# slidi.net
KiCad netlist of a schematic drawn in EAGLE
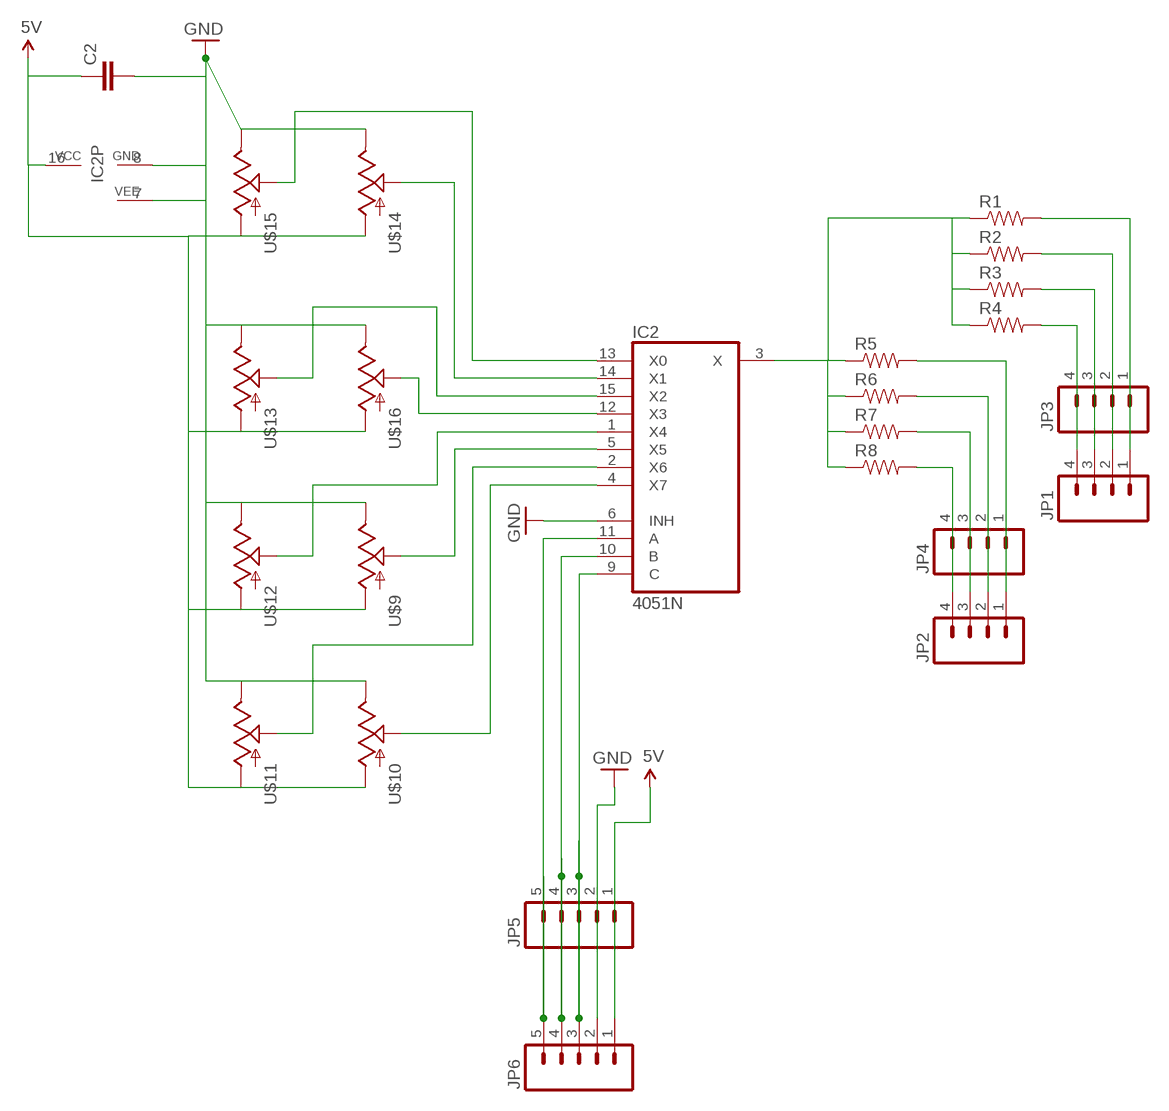
[diagram p0: schematic, sheet 1]

(export (version "E")
  (design (tool "Eeschema 10.0.6"))
  (components
    (comp (ref "C2")
      (value "CAPPTH")
      (footprint "eagle-import:CAP-PTH-SMALL")
      (libsource (lib "eagle-import") (part "CAPPTH"))
    )
    (comp (ref "IC2")
      (value "4051N")
      (footprint "eagle-import:DIL16")
      (libsource (lib "eagle-import") (part "4051N"))
    )
    (comp (ref "JP1")
      (value "M04PTH")
      (footprint "eagle-import:1X04")
      (libsource (lib "eagle-import") (part "M04PTH"))
    )
    (comp (ref "JP2")
      (value "M04PTH")
      (footprint "eagle-import:1X04")
      (libsource (lib "eagle-import") (part "M04PTH"))
    )
    (comp (ref "JP3")
      (value "M04PTH")
      (footprint "eagle-import:1X04")
      (libsource (lib "eagle-import") (part "M04PTH"))
    )
    (comp (ref "JP4")
      (value "M04PTH")
      (footprint "eagle-import:1X04")
      (libsource (lib "eagle-import") (part "M04PTH"))
    )
    (comp (ref "JP5")
      (value "M05PTH")
      (footprint "eagle-import:1X05")
      (libsource (lib "eagle-import") (part "M05PTH"))
    )
    (comp (ref "JP6")
      (value "M05PTH")
      (footprint "eagle-import:1X05")
      (libsource (lib "eagle-import") (part "M05PTH"))
    )
    (comp (ref "R1")
      (value "RESISTORAXIAL-0.3")
      (footprint "eagle-import:AXIAL-0.3")
      (libsource (lib "eagle-import") (part "RESISTORAXIAL-0.3"))
    )
    (comp (ref "R2")
      (value "RESISTORAXIAL-0.3")
      (footprint "eagle-import:AXIAL-0.3")
      (libsource (lib "eagle-import") (part "RESISTORAXIAL-0.3"))
    )
    (comp (ref "R3")
      (value "RESISTORAXIAL-0.3")
      (footprint "eagle-import:AXIAL-0.3")
      (libsource (lib "eagle-import") (part "RESISTORAXIAL-0.3"))
    )
    (comp (ref "R4")
      (value "RESISTORAXIAL-0.3")
      (footprint "eagle-import:AXIAL-0.3")
      (libsource (lib "eagle-import") (part "RESISTORAXIAL-0.3"))
    )
    (comp (ref "R5")
      (value "RESISTORAXIAL-0.3")
      (footprint "eagle-import:AXIAL-0.3")
      (libsource (lib "eagle-import") (part "RESISTORAXIAL-0.3"))
    )
    (comp (ref "R6")
      (value "RESISTORAXIAL-0.3")
      (footprint "eagle-import:AXIAL-0.3")
      (libsource (lib "eagle-import") (part "RESISTORAXIAL-0.3"))
    )
    (comp (ref "R7")
      (value "RESISTORAXIAL-0.3")
      (footprint "eagle-import:AXIAL-0.3")
      (libsource (lib "eagle-import") (part "RESISTORAXIAL-0.3"))
    )
    (comp (ref "R8")
      (value "RESISTORAXIAL-0.3")
      (footprint "eagle-import:AXIAL-0.3")
      (libsource (lib "eagle-import") (part "RESISTORAXIAL-0.3"))
    )
    (comp (ref "U$9")
      (value "SLIDEPOT")
      (footprint "eagle-import:SLIDEPOT")
      (libsource (lib "eagle-import") (part "SLIDEPOT"))
    )
    (comp (ref "U$10")
      (value "SLIDEPOT")
      (footprint "eagle-import:SLIDEPOT")
      (libsource (lib "eagle-import") (part "SLIDEPOT"))
    )
    (comp (ref "U$11")
      (value "SLIDEPOT")
      (footprint "eagle-import:SLIDEPOT")
      (libsource (lib "eagle-import") (part "SLIDEPOT"))
    )
    (comp (ref "U$12")
      (value "SLIDEPOT")
      (footprint "eagle-import:SLIDEPOT")
      (libsource (lib "eagle-import") (part "SLIDEPOT"))
    )
    (comp (ref "U$13")
      (value "SLIDEPOT")
      (footprint "eagle-import:SLIDEPOT")
      (libsource (lib "eagle-import") (part "SLIDEPOT"))
    )
    (comp (ref "U$14")
      (value "SLIDEPOT")
      (footprint "eagle-import:SLIDEPOT")
      (libsource (lib "eagle-import") (part "SLIDEPOT"))
    )
    (comp (ref "U$15")
      (value "SLIDEPOT")
      (footprint "eagle-import:SLIDEPOT")
      (libsource (lib "eagle-import") (part "SLIDEPOT"))
    )
    (comp (ref "U$16")
      (value "SLIDEPOT")
      (footprint "eagle-import:SLIDEPOT")
      (libsource (lib "eagle-import") (part "SLIDEPOT"))
    )
  )
  (nets
    (net (code "1") (name "5V") (class "Default")
      (node (ref "C2") (pin "1") (pinfunction "1_1") (pintype "passive"))
      (node (ref "IC2") (pin "16") (pinfunction "VCC_16") (pintype "power_in"))
      (node (ref "JP5") (pin "1") (pinfunction "1_1") (pintype "passive"))
      (node (ref "JP6") (pin "1") (pinfunction "1_1") (pintype "passive"))
      (node (ref "U$10") (pin "GND") (pinfunction "A_GND") (pintype "passive"))
      (node (ref "U$11") (pin "GND") (pinfunction "A_GND") (pintype "passive"))
      (node (ref "U$12") (pin "GND") (pinfunction "A_GND") (pintype "passive"))
      (node (ref "U$13") (pin "GND") (pinfunction "A_GND") (pintype "passive"))
      (node (ref "U$14") (pin "GND") (pinfunction "A_GND") (pintype "passive"))
      (node (ref "U$15") (pin "GND") (pinfunction "A_GND") (pintype "passive"))
      (node (ref "U$16") (pin "GND") (pinfunction "A_GND") (pintype "passive"))
      (node (ref "U$9") (pin "GND") (pinfunction "A_GND") (pintype "passive"))
    )
    (net (code "2") (name "GND") (class "Default")
      (node (ref "C2") (pin "2") (pinfunction "2_2") (pintype "passive"))
      (node (ref "IC2") (pin "6") (pinfunction "INH_6") (pintype "input"))
      (node (ref "IC2") (pin "7") (pinfunction "VEE_7") (pintype "power_in"))
      (node (ref "IC2") (pin "8") (pinfunction "GND_8") (pintype "power_in"))
      (node (ref "JP5") (pin "2") (pinfunction "2_2") (pintype "passive"))
      (node (ref "JP6") (pin "2") (pinfunction "2_2") (pintype "passive"))
      (node (ref "U$10") (pin "5V") (pinfunction "E_5V") (pintype "passive"))
      (node (ref "U$11") (pin "5V") (pinfunction "E_5V") (pintype "passive"))
      (node (ref "U$12") (pin "5V") (pinfunction "E_5V") (pintype "passive"))
      (node (ref "U$13") (pin "5V") (pinfunction "E_5V") (pintype "passive"))
      (node (ref "U$14") (pin "5V") (pinfunction "E_5V") (pintype "passive"))
      (node (ref "U$15") (pin "5V") (pinfunction "E_5V") (pintype "passive"))
      (node (ref "U$16") (pin "5V") (pinfunction "E_5V") (pintype "passive"))
      (node (ref "U$9") (pin "5V") (pinfunction "E_5V") (pintype "passive"))
    )
    (net (code "3") (name "Net-(IC2A-A)") (class "Default")
      (node (ref "IC2") (pin "11") (pinfunction "A_11") (pintype "input"))
      (node (ref "JP5") (pin "5") (pinfunction "5_5") (pintype "passive"))
      (node (ref "JP6") (pin "5") (pinfunction "5_5") (pintype "passive"))
    )
    (net (code "4") (name "Net-(IC2A-B)") (class "Default")
      (node (ref "IC2") (pin "10") (pinfunction "B_10") (pintype "input"))
      (node (ref "JP5") (pin "4") (pinfunction "4_4") (pintype "passive"))
      (node (ref "JP6") (pin "4") (pinfunction "4_4") (pintype "passive"))
    )
    (net (code "5") (name "Net-(IC2A-C)") (class "Default")
      (node (ref "IC2") (pin "9") (pinfunction "C_9") (pintype "input"))
      (node (ref "JP5") (pin "3") (pinfunction "3_3") (pintype "passive"))
      (node (ref "JP6") (pin "3") (pinfunction "3_3") (pintype "passive"))
    )
    (net (code "6") (name "Net-(IC2A-X)") (class "Default")
      (node (ref "IC2") (pin "3") (pinfunction "X_3") (pintype "bidirectional"))
      (node (ref "R1") (pin "P$1") (pinfunction "1_P$1") (pintype "passive"))
      (node (ref "R2") (pin "P$1") (pinfunction "1_P$1") (pintype "passive"))
      (node (ref "R3") (pin "P$1") (pinfunction "1_P$1") (pintype "passive"))
      (node (ref "R4") (pin "P$1") (pinfunction "1_P$1") (pintype "passive"))
      (node (ref "R5") (pin "P$1") (pinfunction "1_P$1") (pintype "passive"))
      (node (ref "R6") (pin "P$1") (pinfunction "1_P$1") (pintype "passive"))
      (node (ref "R7") (pin "P$1") (pinfunction "1_P$1") (pintype "passive"))
      (node (ref "R8") (pin "P$1") (pinfunction "1_P$1") (pintype "passive"))
    )
    (net (code "7") (name "Net-(IC2A-X0)") (class "Default")
      (node (ref "IC2") (pin "13") (pinfunction "X0_13") (pintype "bidirectional"))
      (node (ref "U$15") (pin "WIPER") (pinfunction "S_WIPER") (pintype "passive"))
    )
    (net (code "8") (name "Net-(IC2A-X1)") (class "Default")
      (node (ref "IC2") (pin "14") (pinfunction "X1_14") (pintype "bidirectional"))
      (node (ref "U$14") (pin "WIPER") (pinfunction "S_WIPER") (pintype "passive"))
    )
    (net (code "9") (name "Net-(IC2A-X2)") (class "Default")
      (node (ref "IC2") (pin "15") (pinfunction "X2_15") (pintype "bidirectional"))
      (node (ref "U$13") (pin "WIPER") (pinfunction "S_WIPER") (pintype "passive"))
    )
    (net (code "10") (name "Net-(IC2A-X3)") (class "Default")
      (node (ref "IC2") (pin "12") (pinfunction "X3_12") (pintype "bidirectional"))
      (node (ref "U$16") (pin "WIPER") (pinfunction "S_WIPER") (pintype "passive"))
    )
    (net (code "11") (name "Net-(IC2A-X4)") (class "Default")
      (node (ref "IC2") (pin "1") (pinfunction "X4_1") (pintype "bidirectional"))
      (node (ref "U$12") (pin "WIPER") (pinfunction "S_WIPER") (pintype "passive"))
    )
    (net (code "12") (name "Net-(IC2A-X5)") (class "Default")
      (node (ref "IC2") (pin "5") (pinfunction "X5_5") (pintype "bidirectional"))
      (node (ref "U$9") (pin "WIPER") (pinfunction "S_WIPER") (pintype "passive"))
    )
    (net (code "13") (name "Net-(IC2A-X6)") (class "Default")
      (node (ref "IC2") (pin "2") (pinfunction "X6_2") (pintype "bidirectional"))
      (node (ref "U$11") (pin "WIPER") (pinfunction "S_WIPER") (pintype "passive"))
    )
    (net (code "14") (name "Net-(IC2A-X7)") (class "Default")
      (node (ref "IC2") (pin "4") (pinfunction "X7_4") (pintype "bidirectional"))
      (node (ref "U$10") (pin "WIPER") (pinfunction "S_WIPER") (pintype "passive"))
    )
    (net (code "15") (name "Net-(R1-2)") (class "Default")
      (node (ref "JP1") (pin "1") (pinfunction "1_1") (pintype "passive"))
      (node (ref "JP3") (pin "1") (pinfunction "1_1") (pintype "passive"))
      (node (ref "R1") (pin "P$2") (pinfunction "2_P$2") (pintype "passive"))
    )
    (net (code "16") (name "Net-(R2-2)") (class "Default")
      (node (ref "JP1") (pin "2") (pinfunction "2_2") (pintype "passive"))
      (node (ref "JP3") (pin "2") (pinfunction "2_2") (pintype "passive"))
      (node (ref "R2") (pin "P$2") (pinfunction "2_P$2") (pintype "passive"))
    )
    (net (code "17") (name "Net-(R3-2)") (class "Default")
      (node (ref "JP1") (pin "3") (pinfunction "3_3") (pintype "passive"))
      (node (ref "JP3") (pin "3") (pinfunction "3_3") (pintype "passive"))
      (node (ref "R3") (pin "P$2") (pinfunction "2_P$2") (pintype "passive"))
    )
    (net (code "18") (name "Net-(R4-2)") (class "Default")
      (node (ref "JP1") (pin "4") (pinfunction "4_4") (pintype "passive"))
      (node (ref "JP3") (pin "4") (pinfunction "4_4") (pintype "passive"))
      (node (ref "R4") (pin "P$2") (pinfunction "2_P$2") (pintype "passive"))
    )
    (net (code "19") (name "Net-(R5-2)") (class "Default")
      (node (ref "JP2") (pin "1") (pinfunction "1_1") (pintype "passive"))
      (node (ref "JP4") (pin "1") (pinfunction "1_1") (pintype "passive"))
      (node (ref "R5") (pin "P$2") (pinfunction "2_P$2") (pintype "passive"))
    )
    (net (code "20") (name "Net-(R6-2)") (class "Default")
      (node (ref "JP2") (pin "2") (pinfunction "2_2") (pintype "passive"))
      (node (ref "JP4") (pin "2") (pinfunction "2_2") (pintype "passive"))
      (node (ref "R6") (pin "P$2") (pinfunction "2_P$2") (pintype "passive"))
    )
    (net (code "21") (name "Net-(R7-2)") (class "Default")
      (node (ref "JP2") (pin "3") (pinfunction "3_3") (pintype "passive"))
      (node (ref "JP4") (pin "3") (pinfunction "3_3") (pintype "passive"))
      (node (ref "R7") (pin "P$2") (pinfunction "2_P$2") (pintype "passive"))
    )
    (net (code "22") (name "Net-(R8-2)") (class "Default")
      (node (ref "JP2") (pin "4") (pinfunction "4_4") (pintype "passive"))
      (node (ref "JP4") (pin "4") (pinfunction "4_4") (pintype "passive"))
      (node (ref "R8") (pin "P$2") (pinfunction "2_P$2") (pintype "passive"))
    )
  )
)
